# DoorALIM.net
KiCad netlist of a schematic drawn in EAGLE
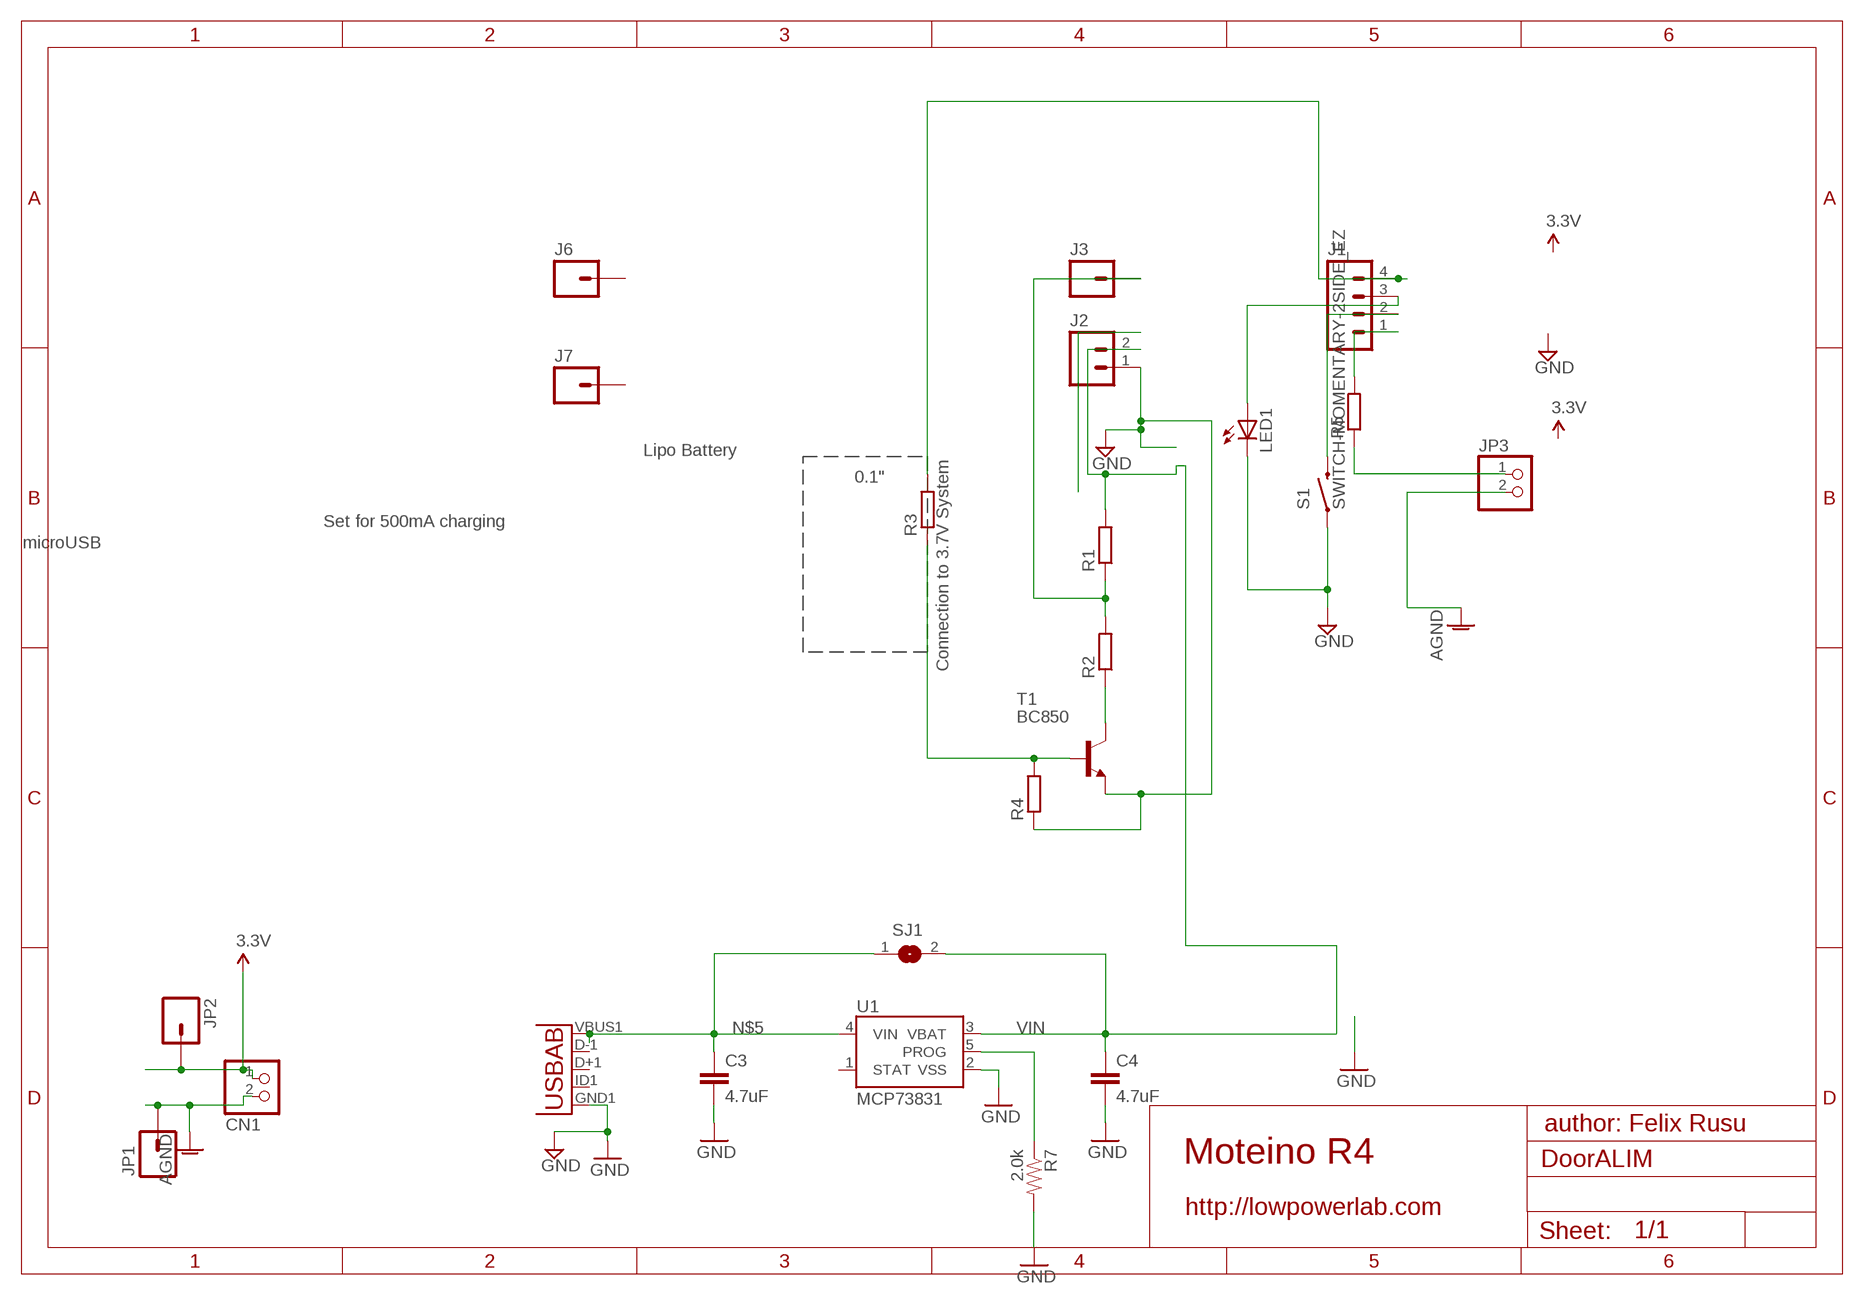
[diagram p0: schematic, sheet 1]

(export (version "E")
  (design (tool "Eeschema 10.0.6"))
  (components
    (comp (ref "C3")
      (value "4.7uF")
      (footprint "eagle-import:0603-CAP")
      (libsource (lib "eagle-import") (part "4.7UF-6.3V-10%(0603)0603"))
    )
    (comp (ref "C4")
      (value "4.7uF")
      (footprint "eagle-import:0603-CAP")
      (libsource (lib "eagle-import") (part "4.7UF-6.3V-10%(0603)0603"))
    )
    (comp (ref "CN1")
      (value "JST_2PIN-SMT")
      (footprint "eagle-import:JST-PH-2-SMT")
      (libsource (lib "eagle-import") (part "JST_2PIN-SMT"))
    )
    (comp (ref "J1")
      (value "M04PTH")
      (footprint "eagle-import:1X04")
      (libsource (lib "eagle-import") (part "M04PTH"))
    )
    (comp (ref "J2")
      (value "M02PTH")
      (footprint "eagle-import:1X02")
      (libsource (lib "eagle-import") (part "M02PTH"))
    )
    (comp (ref "J3")
      (value "M01PTH")
      (footprint "eagle-import:1X01")
      (libsource (lib "eagle-import") (part "M01PTH"))
    )
    (comp (ref "J6")
      (value "M01PTH")
      (footprint "eagle-import:1X01")
      (libsource (lib "eagle-import") (part "M01PTH"))
    )
    (comp (ref "J7")
      (value "M01PTH")
      (footprint "eagle-import:1X01")
      (libsource (lib "eagle-import") (part "M01PTH"))
    )
    (comp (ref "JP1")
      (value "M01PTH")
      (footprint "eagle-import:1X01")
      (libsource (lib "eagle-import") (part "M01PTH"))
    )
    (comp (ref "JP2")
      (value "M01PTH")
      (footprint "eagle-import:1X01")
      (libsource (lib "eagle-import") (part "M01PTH"))
    )
    (comp (ref "JP3")
      (value "PINHD-1X2")
      (footprint "eagle-import:1X02")
      (libsource (lib "eagle-import") (part "PINHD-1X2"))
    )
    (comp (ref "JP9")
      (value "Micro USB")
      (footprint "eagle-import:USB-AB-MICRO-SMD_V03")
      (libsource (lib "eagle-import") (part "USB-ABCONN-11794"))
    )
    (comp (ref "LED1")
      (value "LED3MM")
      (footprint "eagle-import:LED3MM")
      (libsource (lib "eagle-import") (part "LED3MM"))
    )
    (comp (ref "R1")
      (value "R-EU_0204/7")
      (footprint "eagle-import:0204_7")
      (libsource (lib "eagle-import") (part "R-EU_0204/7"))
    )
    (comp (ref "R2")
      (value "R-EU_0204/7")
      (footprint "eagle-import:0204_7")
      (libsource (lib "eagle-import") (part "R-EU_0204/7"))
    )
    (comp (ref "R3")
      (value "R-EU_M1206")
      (footprint "eagle-import:M1206")
      (libsource (lib "eagle-import") (part "R-EU_M1206"))
    )
    (comp (ref "R4")
      (value "R-EU_M1206")
      (footprint "eagle-import:M1206")
      (libsource (lib "eagle-import") (part "R-EU_M1206"))
    )
    (comp (ref "R5")
      (value "R-EU_0204/7")
      (footprint "eagle-import:0204_7")
      (libsource (lib "eagle-import") (part "R-EU_0204/7"))
    )
    (comp (ref "R7")
      (value "2.0k")
      (footprint "eagle-import:0603-RES")
      (libsource (lib "eagle-import") (part "2.0KOHM1/10W5%(0603)"))
    )
    (comp (ref "S1")
      (value "SWITCH-MOMENTARY-2SIDE_EZ")
      (footprint "eagle-import:TACTILE-PTH-SIDEEZ")
      (libsource (lib "eagle-import") (part "SWITCH-MOMENTARY-2SIDE_EZ"))
    )
    (comp (ref "SJ1") (value "SJ") (footprint "eagle-import:SJ") (libsource (lib "eagle-import") (part "SJ")))
    (comp (ref "T1")
      (value "BC850")
      (footprint "eagle-import:SOT23")
      (libsource (lib "eagle-import") (part "BC850"))
    )
    (comp (ref "U1")
      (value "MCP73831")
      (footprint "eagle-import:SOT23-5")
      (libsource (lib "eagle-import") (part "MCP73831"))
    )
  )
  (nets
    (net (code "1") (name "/N$5") (class "Default")
      (node (ref "C3") (pin "1") (pinfunction "1_1") (pintype "passive"))
      (node (ref "JP9") (pin "VBUS1") (pinfunction "VBUS_VBUS1") (pintype "bidirectional"))
      (node (ref "SJ1") (pin "1") (pinfunction "1_1") (pintype "passive"))
      (node (ref "U1") (pin "4") (pinfunction "VIN_4") (pintype "power_in"))
    )
    (net (code "2") (name "/VIN") (class "Default")
      (node (ref "C4") (pin "1") (pinfunction "1_1") (pintype "passive"))
      (node (ref "J2") (pin "2") (pinfunction "2_2") (pintype "passive"))
      (node (ref "R1") (pin "2") (pinfunction "2_2") (pintype "passive"))
      (node (ref "SJ1") (pin "2") (pinfunction "2_2") (pintype "passive"))
      (node (ref "U1") (pin "3") (pinfunction "VBAT_3") (pintype "power_in"))
    )
    (net (code "3") (name "3.3V") (class "Default")
      (node (ref "CN1") (pin "1") (pinfunction "2_1") (pintype "passive"))
      (node (ref "JP2") (pin "1") (pinfunction "1_1") (pintype "passive"))
    )
    (net (code "4") (name "AGND") (class "Default")
      (node (ref "CN1") (pin "2") (pinfunction "1_2") (pintype "passive"))
      (node (ref "JP1") (pin "1") (pinfunction "1_1") (pintype "passive"))
      (node (ref "JP3") (pin "2") (pinfunction "2_2") (pintype "passive"))
    )
    (net (code "5") (name "GND") (class "Default")
      (node (ref "C3") (pin "2") (pinfunction "2_2") (pintype "passive"))
      (node (ref "C4") (pin "2") (pinfunction "2_2") (pintype "passive"))
      (node (ref "J2") (pin "1") (pinfunction "1_1") (pintype "passive"))
      (node (ref "JP9") (pin "GND1") (pinfunction "GND_GND1") (pintype "bidirectional"))
      (node (ref "LED1") (pin "K") (pinfunction "C_K") (pintype "passive"))
      (node (ref "R4") (pin "1") (pinfunction "1_1") (pintype "passive"))
      (node (ref "R7") (pin "2") (pinfunction "2_2") (pintype "passive"))
      (node (ref "S1") (pin "1") (pinfunction "1_1") (pintype "passive"))
      (node (ref "T1") (pin "2") (pinfunction "E_2") (pintype "passive"))
      (node (ref "U1") (pin "2") (pinfunction "VSS_2") (pintype "power_in"))
    )
    (net (code "6") (name "Net-(J1-Pad1)") (class "Default")
      (node (ref "J1") (pin "1") (pinfunction "1_1") (pintype "passive"))
      (node (ref "R5") (pin "2") (pinfunction "2_2") (pintype "passive"))
    )
    (net (code "7") (name "Net-(J1-Pad2)") (class "Default")
      (node (ref "J1") (pin "2") (pinfunction "2_2") (pintype "passive"))
      (node (ref "S1") (pin "2") (pinfunction "2_2") (pintype "passive"))
    )
    (net (code "8") (name "Net-(J1-Pad3)") (class "Default")
      (node (ref "J1") (pin "3") (pinfunction "3_3") (pintype "passive"))
      (node (ref "LED1") (pin "A") (pinfunction "A_A") (pintype "passive"))
    )
    (net (code "9") (name "Net-(J1-Pad4)") (class "Default")
      (node (ref "J1") (pin "4") (pinfunction "4_4") (pintype "passive"))
      (node (ref "R3") (pin "2") (pinfunction "2_2") (pintype "passive"))
    )
    (net (code "10") (name "Net-(J3-Pad1)") (class "Default")
      (node (ref "J3") (pin "1") (pinfunction "1_1") (pintype "passive"))
      (node (ref "R1") (pin "1") (pinfunction "1_1") (pintype "passive"))
      (node (ref "R2") (pin "2") (pinfunction "2_2") (pintype "passive"))
    )
    (net (code "11") (name "Net-(JP3-Pad1)") (class "Default")
      (node (ref "JP3") (pin "1") (pinfunction "1_1") (pintype "passive"))
      (node (ref "R5") (pin "1") (pinfunction "1_1") (pintype "passive"))
    )
    (net (code "12") (name "Net-(T1-B)") (class "Default")
      (node (ref "R3") (pin "1") (pinfunction "1_1") (pintype "passive"))
      (node (ref "R4") (pin "2") (pinfunction "2_2") (pintype "passive"))
      (node (ref "T1") (pin "1") (pinfunction "B_1") (pintype "passive"))
    )
    (net (code "13") (name "Net-(T1-C)") (class "Default")
      (node (ref "R2") (pin "1") (pinfunction "1_1") (pintype "passive"))
      (node (ref "T1") (pin "3") (pinfunction "C_3") (pintype "passive"))
    )
    (net (code "14") (name "Net-(U1-PROG)") (class "Default")
      (node (ref "R7") (pin "1") (pinfunction "1_1") (pintype "passive"))
      (node (ref "U1") (pin "5") (pinfunction "PROG_5") (pintype "input"))
    )
    (net (code "15") (name "unconnected-(J6-Pad1)") (class "Default")
      (node (ref "J6") (pin "1") (pinfunction "1_1") (pintype "passive"))
    )
    (net (code "16") (name "unconnected-(J7-Pad1)") (class "Default")
      (node (ref "J7") (pin "1") (pinfunction "1_1") (pintype "passive"))
    )
    (net (code "17") (name "unconnected-(JP9-D+-PadD+1)") (class "Default")
      (node (ref "JP9") (pin "D+1") (pinfunction "D+_D+1") (pintype "bidirectional"))
    )
    (net (code "18") (name "unconnected-(JP9-D--PadD-1)") (class "Default")
      (node (ref "JP9") (pin "D-1") (pinfunction "D-_D-1") (pintype "bidirectional"))
    )
    (net (code "19") (name "unconnected-(JP9-USBID-PadID1)") (class "Default")
      (node (ref "JP9") (pin "ID1") (pinfunction "USBID_ID1") (pintype "bidirectional"))
    )
    (net (code "20") (name "unconnected-(U1-STAT-Pad1)") (class "Default")
      (node (ref "U1") (pin "1") (pinfunction "STAT_1") (pintype "output"))
    )
  )
)
